# TTGO_shield_revA.net
KiCad netlist of a schematic drawn in EAGLE
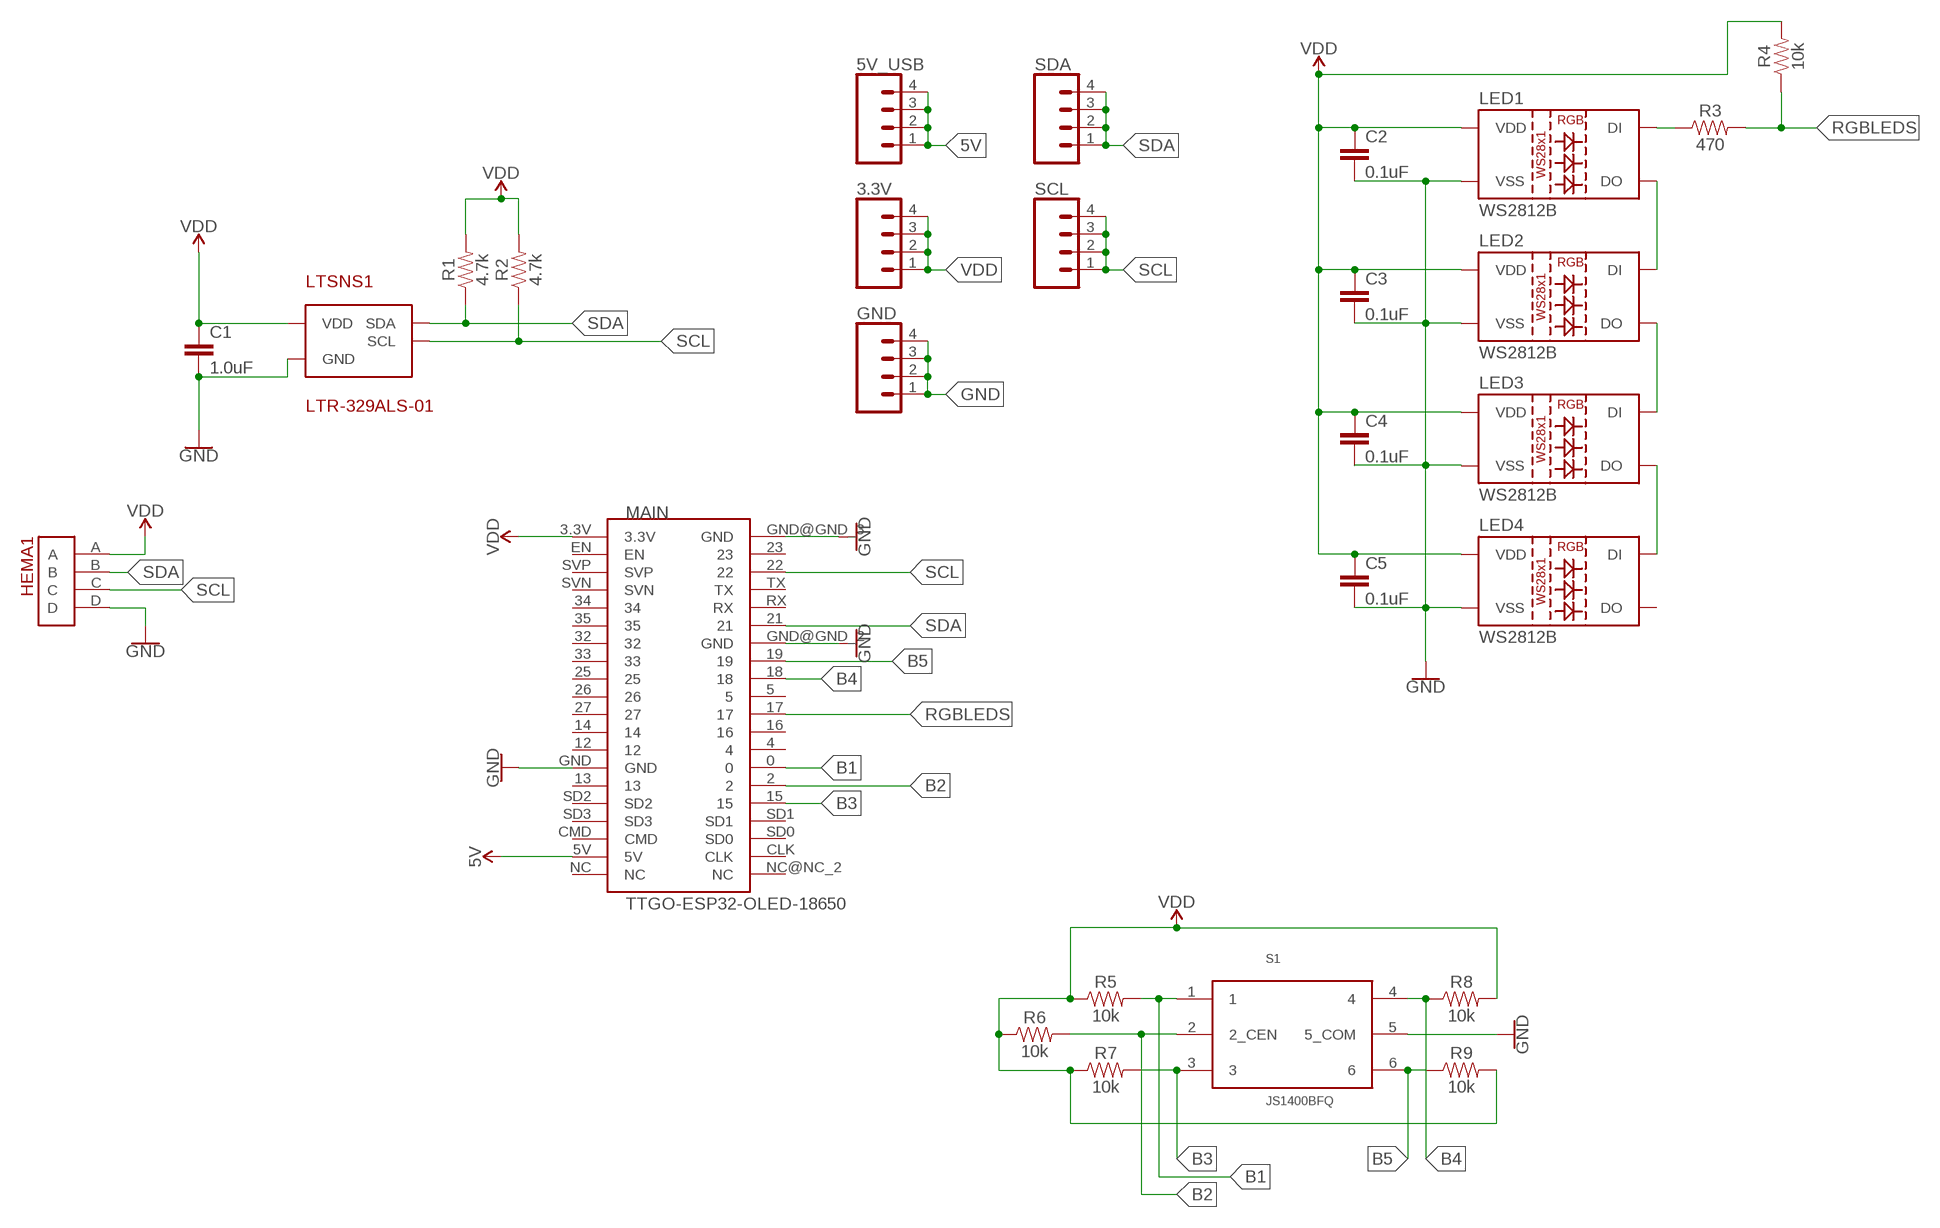
[diagram p0: schematic, sheet 1]

(export (version "E")
  (design (tool "Eeschema 10.0.6"))
  (components
    (comp (ref "3.3V")
      (value "CONN_041X04_NO_SILK")
      (footprint "eagle-import:1X04_NO_SILK")
      (libsource (lib "eagle-import") (part "CONN_041X04_NO_SILK"))
    )
    (comp (ref "5V_USB")
      (value "CONN_041X04_NO_SILK")
      (footprint "eagle-import:1X04_NO_SILK")
      (libsource (lib "eagle-import") (part "CONN_041X04_NO_SILK"))
    )
    (comp (ref "C1")
      (value "1.0uF")
      (footprint "eagle-import:0805")
      (libsource (lib "eagle-import") (part "1.0UF-0805-25V-10%"))
    )
    (comp (ref "C2")
      (value "0.1uF")
      (footprint "eagle-import:0603")
      (libsource (lib "eagle-import") (part "0.1UF-0603-25V-5%"))
    )
    (comp (ref "C3")
      (value "0.1uF")
      (footprint "eagle-import:0603")
      (libsource (lib "eagle-import") (part "0.1UF-0603-25V-5%"))
    )
    (comp (ref "C4")
      (value "0.1uF")
      (footprint "eagle-import:0603")
      (libsource (lib "eagle-import") (part "0.1UF-0603-25V-5%"))
    )
    (comp (ref "C5")
      (value "0.1uF")
      (footprint "eagle-import:0603")
      (libsource (lib "eagle-import") (part "0.1UF-0603-25V-5%"))
    )
    (comp (ref "GND")
      (value "CONN_041X04_NO_SILK")
      (footprint "eagle-import:1X04_NO_SILK")
      (libsource (lib "eagle-import") (part "CONN_041X04_NO_SILK"))
    )
    (comp (ref "HEMA1")
      (value "10120045-400LF")
      (footprint "eagle-import:10120045-400LF")
      (libsource (lib "eagle-import") (part "10120045-400LF"))
    )
    (comp (ref "LED1")
      (value "WS2812B")
      (footprint "eagle-import:WS2812B")
      (libsource (lib "eagle-import") (part "WS2812B"))
    )
    (comp (ref "LED2")
      (value "WS2812B")
      (footprint "eagle-import:WS2812B")
      (libsource (lib "eagle-import") (part "WS2812B"))
    )
    (comp (ref "LED3")
      (value "WS2812B")
      (footprint "eagle-import:WS2812B")
      (libsource (lib "eagle-import") (part "WS2812B"))
    )
    (comp (ref "LED4")
      (value "WS2812B")
      (footprint "eagle-import:WS2812B")
      (libsource (lib "eagle-import") (part "WS2812B"))
    )
    (comp (ref "LTSNS1")
      (value "LTR-329ALS-01")
      (footprint "eagle-import:CHIPLED-4")
      (libsource (lib "eagle-import") (part "LTR-329ALS-01"))
    )
    (comp (ref "MAIN")
      (value "TTGO-ESP32-OLED-18650")
      (footprint "eagle-import:TTGO-ESP32-OLED-18650")
      (libsource (lib "eagle-import") (part "TTGO-ESP32-OLED-18650"))
    )
    (comp (ref "R1")
      (value "4.7k")
      (footprint "eagle-import:0603")
      (libsource (lib "eagle-import") (part "4.7KOHM-0603-1/10W-1%"))
    )
    (comp (ref "R2")
      (value "4.7k")
      (footprint "eagle-import:0603")
      (libsource (lib "eagle-import") (part "4.7KOHM-0603-1/10W-1%"))
    )
    (comp (ref "R3")
      (value "470")
      (footprint "eagle-import:0603")
      (libsource (lib "eagle-import") (part "470OHM-0603-1/10W-1%"))
    )
    (comp (ref "R4")
      (value "10k")
      (footprint "eagle-import:0603")
      (libsource (lib "eagle-import") (part "10KOHM-0603-1/10W-1%"))
    )
    (comp (ref "R5")
      (value "10k")
      (footprint "eagle-import:0603")
      (libsource (lib "eagle-import") (part "10KOHM-0603-1/10W-1%"))
    )
    (comp (ref "R6")
      (value "10k")
      (footprint "eagle-import:0603")
      (libsource (lib "eagle-import") (part "10KOHM-0603-1/10W-1%"))
    )
    (comp (ref "R7")
      (value "10k")
      (footprint "eagle-import:0603")
      (libsource (lib "eagle-import") (part "10KOHM-0603-1/10W-1%"))
    )
    (comp (ref "R8")
      (value "10k")
      (footprint "eagle-import:0603")
      (libsource (lib "eagle-import") (part "10KOHM-0603-1/10W-1%"))
    )
    (comp (ref "R9")
      (value "10k")
      (footprint "eagle-import:0603")
      (libsource (lib "eagle-import") (part "10KOHM-0603-1/10W-1%"))
    )
    (comp (ref "S1")
      (value "JS1400BFQ")
      (footprint "eagle-import:JS1400BFQ")
      (libsource (lib "eagle-import") (part "JS1400BFQ"))
    )
    (comp (ref "SCL")
      (value "CONN_041X04_NO_SILK")
      (footprint "eagle-import:1X04_NO_SILK")
      (libsource (lib "eagle-import") (part "CONN_041X04_NO_SILK"))
    )
    (comp (ref "SDA")
      (value "CONN_041X04_NO_SILK")
      (footprint "eagle-import:1X04_NO_SILK")
      (libsource (lib "eagle-import") (part "CONN_041X04_NO_SILK"))
    )
  )
  (nets
    (net (code "1") (name "5V") (class "Default")
      (node (ref "5V_USB") (pin "1") (pinfunction "1_1") (pintype "passive"))
      (node (ref "5V_USB") (pin "2") (pinfunction "2_2") (pintype "passive"))
      (node (ref "5V_USB") (pin "3") (pinfunction "3_3") (pintype "passive"))
      (node (ref "5V_USB") (pin "4") (pinfunction "4_4") (pintype "passive"))
      (node (ref "MAIN") (pin "5V") (pinfunction "5V_5V") (pintype "bidirectional"))
    )
    (net (code "2") (name "B1") (class "Default")
      (node (ref "MAIN") (pin "0") (pinfunction "0_0") (pintype "bidirectional"))
      (node (ref "R5") (pin "2") (pinfunction "2_2") (pintype "passive"))
      (node (ref "S1") (pin "1") (pinfunction "1_1") (pintype "bidirectional"))
    )
    (net (code "3") (name "B2") (class "Default")
      (node (ref "MAIN") (pin "2") (pinfunction "2_2") (pintype "bidirectional"))
      (node (ref "R6") (pin "2") (pinfunction "2_2") (pintype "passive"))
      (node (ref "S1") (pin "2") (pinfunction "2_CEN_2") (pintype "bidirectional"))
    )
    (net (code "4") (name "B3") (class "Default")
      (node (ref "MAIN") (pin "15") (pinfunction "15_15") (pintype "bidirectional"))
      (node (ref "R7") (pin "2") (pinfunction "2_2") (pintype "passive"))
      (node (ref "S1") (pin "3") (pinfunction "3_3") (pintype "bidirectional"))
    )
    (net (code "5") (name "B4") (class "Default")
      (node (ref "MAIN") (pin "18") (pinfunction "18_18") (pintype "bidirectional"))
      (node (ref "R8") (pin "1") (pinfunction "1_1") (pintype "passive"))
      (node (ref "S1") (pin "4") (pinfunction "4_4") (pintype "bidirectional"))
    )
    (net (code "6") (name "B5") (class "Default")
      (node (ref "MAIN") (pin "19") (pinfunction "19_19") (pintype "bidirectional"))
      (node (ref "R9") (pin "1") (pinfunction "1_1") (pintype "passive"))
      (node (ref "S1") (pin "6") (pinfunction "6_6") (pintype "bidirectional"))
    )
    (net (code "7") (name "GND") (class "Default")
      (node (ref "C1") (pin "2") (pinfunction "2_2") (pintype "passive"))
      (node (ref "C2") (pin "2") (pinfunction "2_2") (pintype "passive"))
      (node (ref "C3") (pin "2") (pinfunction "2_2") (pintype "passive"))
      (node (ref "C4") (pin "2") (pinfunction "2_2") (pintype "passive"))
      (node (ref "C5") (pin "2") (pinfunction "2_2") (pintype "passive"))
      (node (ref "GND") (pin "1") (pinfunction "1_1") (pintype "passive"))
      (node (ref "GND") (pin "2") (pinfunction "2_2") (pintype "passive"))
      (node (ref "GND") (pin "3") (pinfunction "3_3") (pintype "passive"))
      (node (ref "GND") (pin "4") (pinfunction "4_4") (pintype "passive"))
      (node (ref "HEMA1") (pin "D") (pinfunction "D_D") (pintype "bidirectional"))
      (node (ref "LED1") (pin "3") (pinfunction "VSS_3") (pintype "bidirectional"))
      (node (ref "LED2") (pin "3") (pinfunction "VSS_3") (pintype "bidirectional"))
      (node (ref "LED3") (pin "3") (pinfunction "VSS_3") (pintype "bidirectional"))
      (node (ref "LED4") (pin "3") (pinfunction "VSS_3") (pintype "bidirectional"))
      (node (ref "LTSNS1") (pin "2") (pinfunction "GND_2") (pintype "bidirectional"))
      (node (ref "MAIN") (pin "GND") (pinfunction "GND_GND") (pintype "bidirectional"))
      (node (ref "MAIN") (pin "GND@GND_2") (pinfunction "GND_GND@GND_2") (pintype "bidirectional"))
      (node (ref "MAIN") (pin "GND@GND_3") (pinfunction "GND_GND@GND_3") (pintype "bidirectional"))
      (node (ref "S1") (pin "5") (pinfunction "5_COM_5") (pintype "bidirectional"))
    )
    (net (code "8") (name "Net-(LED1-DI)") (class "Default")
      (node (ref "LED1") (pin "4") (pinfunction "DI_4") (pintype "bidirectional"))
      (node (ref "R3") (pin "1") (pinfunction "1_1") (pintype "passive"))
    )
    (net (code "9") (name "Net-(LED1-DO)") (class "Default")
      (node (ref "LED1") (pin "2") (pinfunction "DO_2") (pintype "bidirectional"))
      (node (ref "LED2") (pin "4") (pinfunction "DI_4") (pintype "bidirectional"))
    )
    (net (code "10") (name "Net-(LED2-DO)") (class "Default")
      (node (ref "LED2") (pin "2") (pinfunction "DO_2") (pintype "bidirectional"))
      (node (ref "LED3") (pin "4") (pinfunction "DI_4") (pintype "bidirectional"))
    )
    (net (code "11") (name "Net-(LED3-DO)") (class "Default")
      (node (ref "LED3") (pin "2") (pinfunction "DO_2") (pintype "bidirectional"))
      (node (ref "LED4") (pin "4") (pinfunction "DI_4") (pintype "bidirectional"))
    )
    (net (code "12") (name "RGBLEDS") (class "Default")
      (node (ref "MAIN") (pin "17") (pinfunction "17_17") (pintype "bidirectional"))
      (node (ref "R3") (pin "2") (pinfunction "2_2") (pintype "passive"))
      (node (ref "R4") (pin "1") (pinfunction "1_1") (pintype "passive"))
    )
    (net (code "13") (name "SCL") (class "Default")
      (node (ref "HEMA1") (pin "C") (pinfunction "C_C") (pintype "bidirectional"))
      (node (ref "LTSNS1") (pin "4") (pinfunction "SCL_4") (pintype "bidirectional"))
      (node (ref "MAIN") (pin "22") (pinfunction "22_22") (pintype "bidirectional"))
      (node (ref "R2") (pin "1") (pinfunction "1_1") (pintype "passive"))
      (node (ref "SCL") (pin "1") (pinfunction "1_1") (pintype "passive"))
      (node (ref "SCL") (pin "2") (pinfunction "2_2") (pintype "passive"))
      (node (ref "SCL") (pin "3") (pinfunction "3_3") (pintype "passive"))
      (node (ref "SCL") (pin "4") (pinfunction "4_4") (pintype "passive"))
    )
    (net (code "14") (name "SDA") (class "Default")
      (node (ref "HEMA1") (pin "B") (pinfunction "B_B") (pintype "bidirectional"))
      (node (ref "LTSNS1") (pin "3") (pinfunction "SDA_3") (pintype "bidirectional"))
      (node (ref "MAIN") (pin "21") (pinfunction "21_21") (pintype "bidirectional"))
      (node (ref "R1") (pin "1") (pinfunction "1_1") (pintype "passive"))
      (node (ref "SDA") (pin "1") (pinfunction "1_1") (pintype "passive"))
      (node (ref "SDA") (pin "2") (pinfunction "2_2") (pintype "passive"))
      (node (ref "SDA") (pin "3") (pinfunction "3_3") (pintype "passive"))
      (node (ref "SDA") (pin "4") (pinfunction "4_4") (pintype "passive"))
    )
    (net (code "15") (name "VDD") (class "Default")
      (node (ref "3.3V") (pin "1") (pinfunction "1_1") (pintype "passive"))
      (node (ref "3.3V") (pin "2") (pinfunction "2_2") (pintype "passive"))
      (node (ref "3.3V") (pin "3") (pinfunction "3_3") (pintype "passive"))
      (node (ref "3.3V") (pin "4") (pinfunction "4_4") (pintype "passive"))
      (node (ref "C1") (pin "1") (pinfunction "1_1") (pintype "passive"))
      (node (ref "C2") (pin "1") (pinfunction "1_1") (pintype "passive"))
      (node (ref "C3") (pin "1") (pinfunction "1_1") (pintype "passive"))
      (node (ref "C4") (pin "1") (pinfunction "1_1") (pintype "passive"))
      (node (ref "C5") (pin "1") (pinfunction "1_1") (pintype "passive"))
      (node (ref "HEMA1") (pin "A") (pinfunction "A_A") (pintype "bidirectional"))
      (node (ref "LED1") (pin "1") (pinfunction "VDD_1") (pintype "bidirectional"))
      (node (ref "LED2") (pin "1") (pinfunction "VDD_1") (pintype "bidirectional"))
      (node (ref "LED3") (pin "1") (pinfunction "VDD_1") (pintype "bidirectional"))
      (node (ref "LED4") (pin "1") (pinfunction "VDD_1") (pintype "bidirectional"))
      (node (ref "LTSNS1") (pin "1") (pinfunction "VDD_1") (pintype "bidirectional"))
      (node (ref "MAIN") (pin "3.3V") (pinfunction "3.3V_3.3V") (pintype "bidirectional"))
      (node (ref "R1") (pin "2") (pinfunction "2_2") (pintype "passive"))
      (node (ref "R2") (pin "2") (pinfunction "2_2") (pintype "passive"))
      (node (ref "R4") (pin "2") (pinfunction "2_2") (pintype "passive"))
      (node (ref "R5") (pin "1") (pinfunction "1_1") (pintype "passive"))
      (node (ref "R6") (pin "1") (pinfunction "1_1") (pintype "passive"))
      (node (ref "R7") (pin "1") (pinfunction "1_1") (pintype "passive"))
      (node (ref "R8") (pin "2") (pinfunction "2_2") (pintype "passive"))
      (node (ref "R9") (pin "2") (pinfunction "2_2") (pintype "passive"))
    )
    (net (code "16") (name "unconnected-(LED4-DO-Pad2)") (class "Default")
      (node (ref "LED4") (pin "2") (pinfunction "DO_2") (pintype "bidirectional"))
    )
    (net (code "17") (name "unconnected-(MAIN-NC-PadNC@NC_2)") (class "Default")
      (node (ref "MAIN") (pin "NC@NC_2") (pinfunction "NC_NC@NC_2") (pintype "bidirectional"))
    )
    (net (code "18") (name "unconnected-(MAIN-Pad4)") (class "Default")
      (node (ref "MAIN") (pin "4") (pinfunction "4_4") (pintype "bidirectional"))
    )
    (net (code "19") (name "unconnected-(MAIN-Pad5)") (class "Default")
      (node (ref "MAIN") (pin "5") (pinfunction "5_5") (pintype "bidirectional"))
    )
    (net (code "20") (name "unconnected-(MAIN-Pad12)") (class "Default")
      (node (ref "MAIN") (pin "12") (pinfunction "12_12") (pintype "bidirectional"))
    )
    (net (code "21") (name "unconnected-(MAIN-Pad13)") (class "Default")
      (node (ref "MAIN") (pin "13") (pinfunction "13_13") (pintype "bidirectional"))
    )
    (net (code "22") (name "unconnected-(MAIN-Pad14)") (class "Default")
      (node (ref "MAIN") (pin "14") (pinfunction "14_14") (pintype "bidirectional"))
    )
    (net (code "23") (name "unconnected-(MAIN-Pad16)") (class "Default")
      (node (ref "MAIN") (pin "16") (pinfunction "16_16") (pintype "bidirectional"))
    )
    (net (code "24") (name "unconnected-(MAIN-Pad23)") (class "Default")
      (node (ref "MAIN") (pin "23") (pinfunction "23_23") (pintype "bidirectional"))
    )
    (net (code "25") (name "unconnected-(MAIN-Pad25)") (class "Default")
      (node (ref "MAIN") (pin "25") (pinfunction "25_25") (pintype "bidirectional"))
    )
    (net (code "26") (name "unconnected-(MAIN-Pad26)") (class "Default")
      (node (ref "MAIN") (pin "26") (pinfunction "26_26") (pintype "bidirectional"))
    )
    (net (code "27") (name "unconnected-(MAIN-Pad27)") (class "Default")
      (node (ref "MAIN") (pin "27") (pinfunction "27_27") (pintype "bidirectional"))
    )
    (net (code "28") (name "unconnected-(MAIN-Pad32)") (class "Default")
      (node (ref "MAIN") (pin "32") (pinfunction "32_32") (pintype "bidirectional"))
    )
    (net (code "29") (name "unconnected-(MAIN-Pad33)") (class "Default")
      (node (ref "MAIN") (pin "33") (pinfunction "33_33") (pintype "bidirectional"))
    )
    (net (code "30") (name "unconnected-(MAIN-Pad34)") (class "Default")
      (node (ref "MAIN") (pin "34") (pinfunction "34_34") (pintype "bidirectional"))
    )
    (net (code "31") (name "unconnected-(MAIN-Pad35)") (class "Default")
      (node (ref "MAIN") (pin "35") (pinfunction "35_35") (pintype "bidirectional"))
    )
    (net (code "32") (name "unconnected-(MAIN-PadCLK)") (class "Default")
      (node (ref "MAIN") (pin "CLK") (pinfunction "CLK_CLK") (pintype "bidirectional"))
    )
    (net (code "33") (name "unconnected-(MAIN-PadCMD)") (class "Default")
      (node (ref "MAIN") (pin "CMD") (pinfunction "CMD_CMD") (pintype "bidirectional"))
    )
    (net (code "34") (name "unconnected-(MAIN-PadEN)") (class "Default")
      (node (ref "MAIN") (pin "EN") (pinfunction "EN_EN") (pintype "bidirectional"))
    )
    (net (code "35") (name "unconnected-(MAIN-PadNC)") (class "Default")
      (node (ref "MAIN") (pin "NC") (pinfunction "NC_NC") (pintype "bidirectional"))
    )
    (net (code "36") (name "unconnected-(MAIN-PadRX)") (class "Default")
      (node (ref "MAIN") (pin "RX") (pinfunction "RX_RX") (pintype "bidirectional"))
    )
    (net (code "37") (name "unconnected-(MAIN-PadSD0)") (class "Default")
      (node (ref "MAIN") (pin "SD0") (pinfunction "SD0_SD0") (pintype "bidirectional"))
    )
    (net (code "38") (name "unconnected-(MAIN-PadSD1)") (class "Default")
      (node (ref "MAIN") (pin "SD1") (pinfunction "SD1_SD1") (pintype "bidirectional"))
    )
    (net (code "39") (name "unconnected-(MAIN-PadSD2)") (class "Default")
      (node (ref "MAIN") (pin "SD2") (pinfunction "SD2_SD2") (pintype "bidirectional"))
    )
    (net (code "40") (name "unconnected-(MAIN-PadSD3)") (class "Default")
      (node (ref "MAIN") (pin "SD3") (pinfunction "SD3_SD3") (pintype "bidirectional"))
    )
    (net (code "41") (name "unconnected-(MAIN-PadSVN)") (class "Default")
      (node (ref "MAIN") (pin "SVN") (pinfunction "SVN_SVN") (pintype "bidirectional"))
    )
    (net (code "42") (name "unconnected-(MAIN-PadSVP)") (class "Default")
      (node (ref "MAIN") (pin "SVP") (pinfunction "SVP_SVP") (pintype "bidirectional"))
    )
    (net (code "43") (name "unconnected-(MAIN-PadTX)") (class "Default")
      (node (ref "MAIN") (pin "TX") (pinfunction "TX_TX") (pintype "bidirectional"))
    )
  )
)
